# hv-surprise.net
KiCad netlist of a schematic drawn in EAGLE
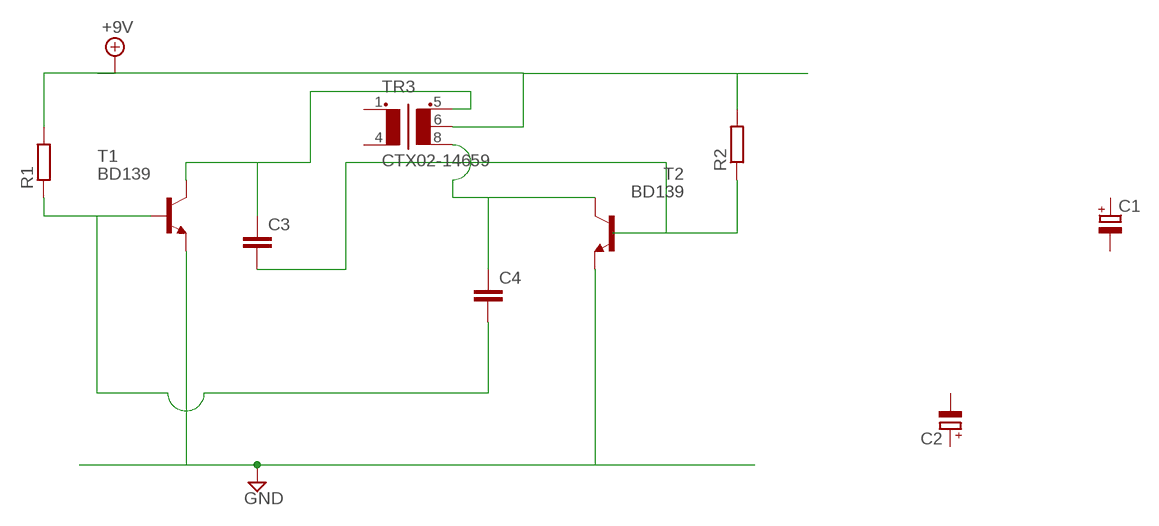
[diagram p0: schematic, sheet 1]

(export (version "E")
  (design (tool "Eeschema 10.0.6"))
  (components
    (comp (ref "C1")
      (value "CPOL-EU153CLV-1010")
      (footprint "eagle-import:153CLV-1010")
      (libsource (lib "eagle-import") (part "CPOL-EU153CLV-1010"))
    )
    (comp (ref "C2")
      (value "CPOL-EU153CLV-1010")
      (footprint "eagle-import:153CLV-1010")
      (libsource (lib "eagle-import") (part "CPOL-EU153CLV-1010"))
    )
    (comp (ref "C3")
      (value "C-EU025-040X050")
      (footprint "eagle-import:C025-040X050")
      (libsource (lib "eagle-import") (part "C-EU025-040X050"))
    )
    (comp (ref "C4")
      (value "C-EU025-040X050")
      (footprint "eagle-import:C025-040X050")
      (libsource (lib "eagle-import") (part "C-EU025-040X050"))
    )
    (comp (ref "R1")
      (value "R-EU_0207/15")
      (footprint "eagle-import:0207_15")
      (libsource (lib "eagle-import") (part "R-EU_0207/15"))
    )
    (comp (ref "R2")
      (value "R-EU_0207/15")
      (footprint "eagle-import:0207_15")
      (libsource (lib "eagle-import") (part "R-EU_0207/15"))
    )
    (comp (ref "T1")
      (value "BD139")
      (footprint "eagle-import:TO126")
      (libsource (lib "eagle-import") (part "BD139"))
    )
    (comp (ref "T2")
      (value "BD139")
      (footprint "eagle-import:TO126")
      (libsource (lib "eagle-import") (part "BD139"))
    )
    (comp (ref "TR3")
      (value "CTX02-14659")
      (footprint "eagle-import:CTX02-14659")
      (libsource (lib "eagle-import") (part "CTX02-14659"))
    )
  )
  (nets
    (net (code "2") (name "GND") (class "Default")
      (node (ref "T1") (pin "1") (pinfunction "E_1") (pintype "passive"))
      (node (ref "T2") (pin "1") (pinfunction "E_1") (pintype "passive"))
    )
    (net (code "3") (name "Net-(C3-Pad2)") (class "Default")
      (node (ref "C3") (pin "2") (pinfunction "2_2") (pintype "passive"))
      (node (ref "R2") (pin "1") (pinfunction "1_1") (pintype "passive"))
    )
    (net (code "4") (name "Net-(T1-B)") (class "Default")
      (node (ref "C4") (pin "2") (pinfunction "2_2") (pintype "passive"))
      (node (ref "R1") (pin "1") (pinfunction "1_1") (pintype "passive"))
      (node (ref "T1") (pin "3") (pinfunction "B_3") (pintype "passive"))
    )
    (net (code "5") (name "Net-(T1-C)") (class "Default")
      (node (ref "C3") (pin "1") (pinfunction "1_1") (pintype "passive"))
      (node (ref "T1") (pin "2") (pinfunction "C_2") (pintype "passive"))
      (node (ref "TR3") (pin "5") (pinfunction "5_5") (pintype "passive"))
    )
    (net (code "6") (name "Net-(T2-C)") (class "Default")
      (node (ref "C4") (pin "1") (pinfunction "1_1") (pintype "passive"))
      (node (ref "T2") (pin "2") (pinfunction "C_2") (pintype "passive"))
      (node (ref "TR3") (pin "8") (pinfunction "3_8") (pintype "passive"))
    )
    (net (code "7") (name "Net-(TR3-4)") (class "Default")
      (node (ref "R1") (pin "2") (pinfunction "2_2") (pintype "passive"))
      (node (ref "R2") (pin "2") (pinfunction "2_2") (pintype "passive"))
      (node (ref "TR3") (pin "6") (pinfunction "4_6") (pintype "passive"))
    )
    (net (code "8") (name "unconnected-(C1-Pad+)") (class "Default")
      (node (ref "C1") (pin "+") (pinfunction "+_+") (pintype "passive"))
    )
    (net (code "9") (name "unconnected-(C1-Pad-)") (class "Default")
      (node (ref "C1") (pin "-") (pinfunction "-_-") (pintype "passive"))
    )
    (net (code "10") (name "unconnected-(C2-Pad+)") (class "Default")
      (node (ref "C2") (pin "+") (pinfunction "+_+") (pintype "passive"))
    )
    (net (code "11") (name "unconnected-(C2-Pad-)") (class "Default")
      (node (ref "C2") (pin "-") (pinfunction "-_-") (pintype "passive"))
    )
    (net (code "12") (name "unconnected-(T2-B-Pad3)") (class "Default")
      (node (ref "T2") (pin "3") (pinfunction "B_3") (pintype "passive"))
    )
    (net (code "13") (name "unconnected-(TR3-2-Pad4)") (class "Default")
      (node (ref "TR3") (pin "4") (pinfunction "2_4") (pintype "passive"))
    )
    (net (code "14") (name "unconnected-(TR3-Pad1)") (class "Default")
      (node (ref "TR3") (pin "1") (pinfunction "1_1") (pintype "passive"))
    )
  )
)
